# turbidity-detect-v0_1.net
KiCad netlist of a schematic drawn in EAGLE
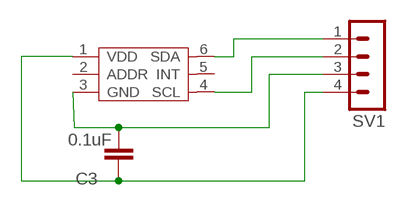
[diagram p0: schematic, sheet 1]

(export (version "E")
  (design (tool "Eeschema 10.0.6"))
  (components
    (comp (ref "C3")
      (value "0.1uF")
      (footprint "eagle-import:0603-CAP")
      (libsource (lib "eagle-import") (part "CAP0603-CAP"))
    )
    (comp (ref "SV1")
      (value "MA04-1")
      (footprint "eagle-import:MA04-1")
      (libsource (lib "eagle-import") (part "MA04-1"))
    )
    (comp (ref "U1")
      (value "TSL2561T")
      (footprint "eagle-import:TMB-6")
      (libsource (lib "eagle-import") (part "TSL2561T"))
    )
  )
  (nets
    (net (code "1") (name "Net-(U1-GND)") (class "Default")
      (node (ref "C3") (pin "1") (pinfunction "1_1") (pintype "passive"))
      (node (ref "SV1") (pin "3") (pinfunction "3_3") (pintype "passive"))
      (node (ref "U1") (pin "3") (pinfunction "GND_3") (pintype "power_in"))
    )
    (net (code "2") (name "Net-(U1-SCL)") (class "Default")
      (node (ref "SV1") (pin "2") (pinfunction "2_2") (pintype "passive"))
      (node (ref "U1") (pin "4") (pinfunction "SCL_4") (pintype "input"))
    )
    (net (code "3") (name "Net-(U1-SDA)") (class "Default")
      (node (ref "SV1") (pin "1") (pinfunction "1_1") (pintype "passive"))
      (node (ref "U1") (pin "6") (pinfunction "SDA_6") (pintype "bidirectional"))
    )
    (net (code "4") (name "Net-(U1-VDD)") (class "Default")
      (node (ref "C3") (pin "2") (pinfunction "2_2") (pintype "passive"))
      (node (ref "SV1") (pin "4") (pinfunction "4_4") (pintype "passive"))
      (node (ref "U1") (pin "1") (pinfunction "VDD_1") (pintype "power_in"))
    )
    (net (code "5") (name "unconnected-(U1-ADDR-Pad2)") (class "Default")
      (node (ref "U1") (pin "2") (pinfunction "ADDR_2") (pintype "input"))
    )
    (net (code "6") (name "unconnected-(U1-INT-Pad5)") (class "Default")
      (node (ref "U1") (pin "5") (pinfunction "INT_5") (pintype "output"))
    )
  )
)
